# hacking_the_simplespectro.net
KiCad netlist of a schematic drawn in EAGLE
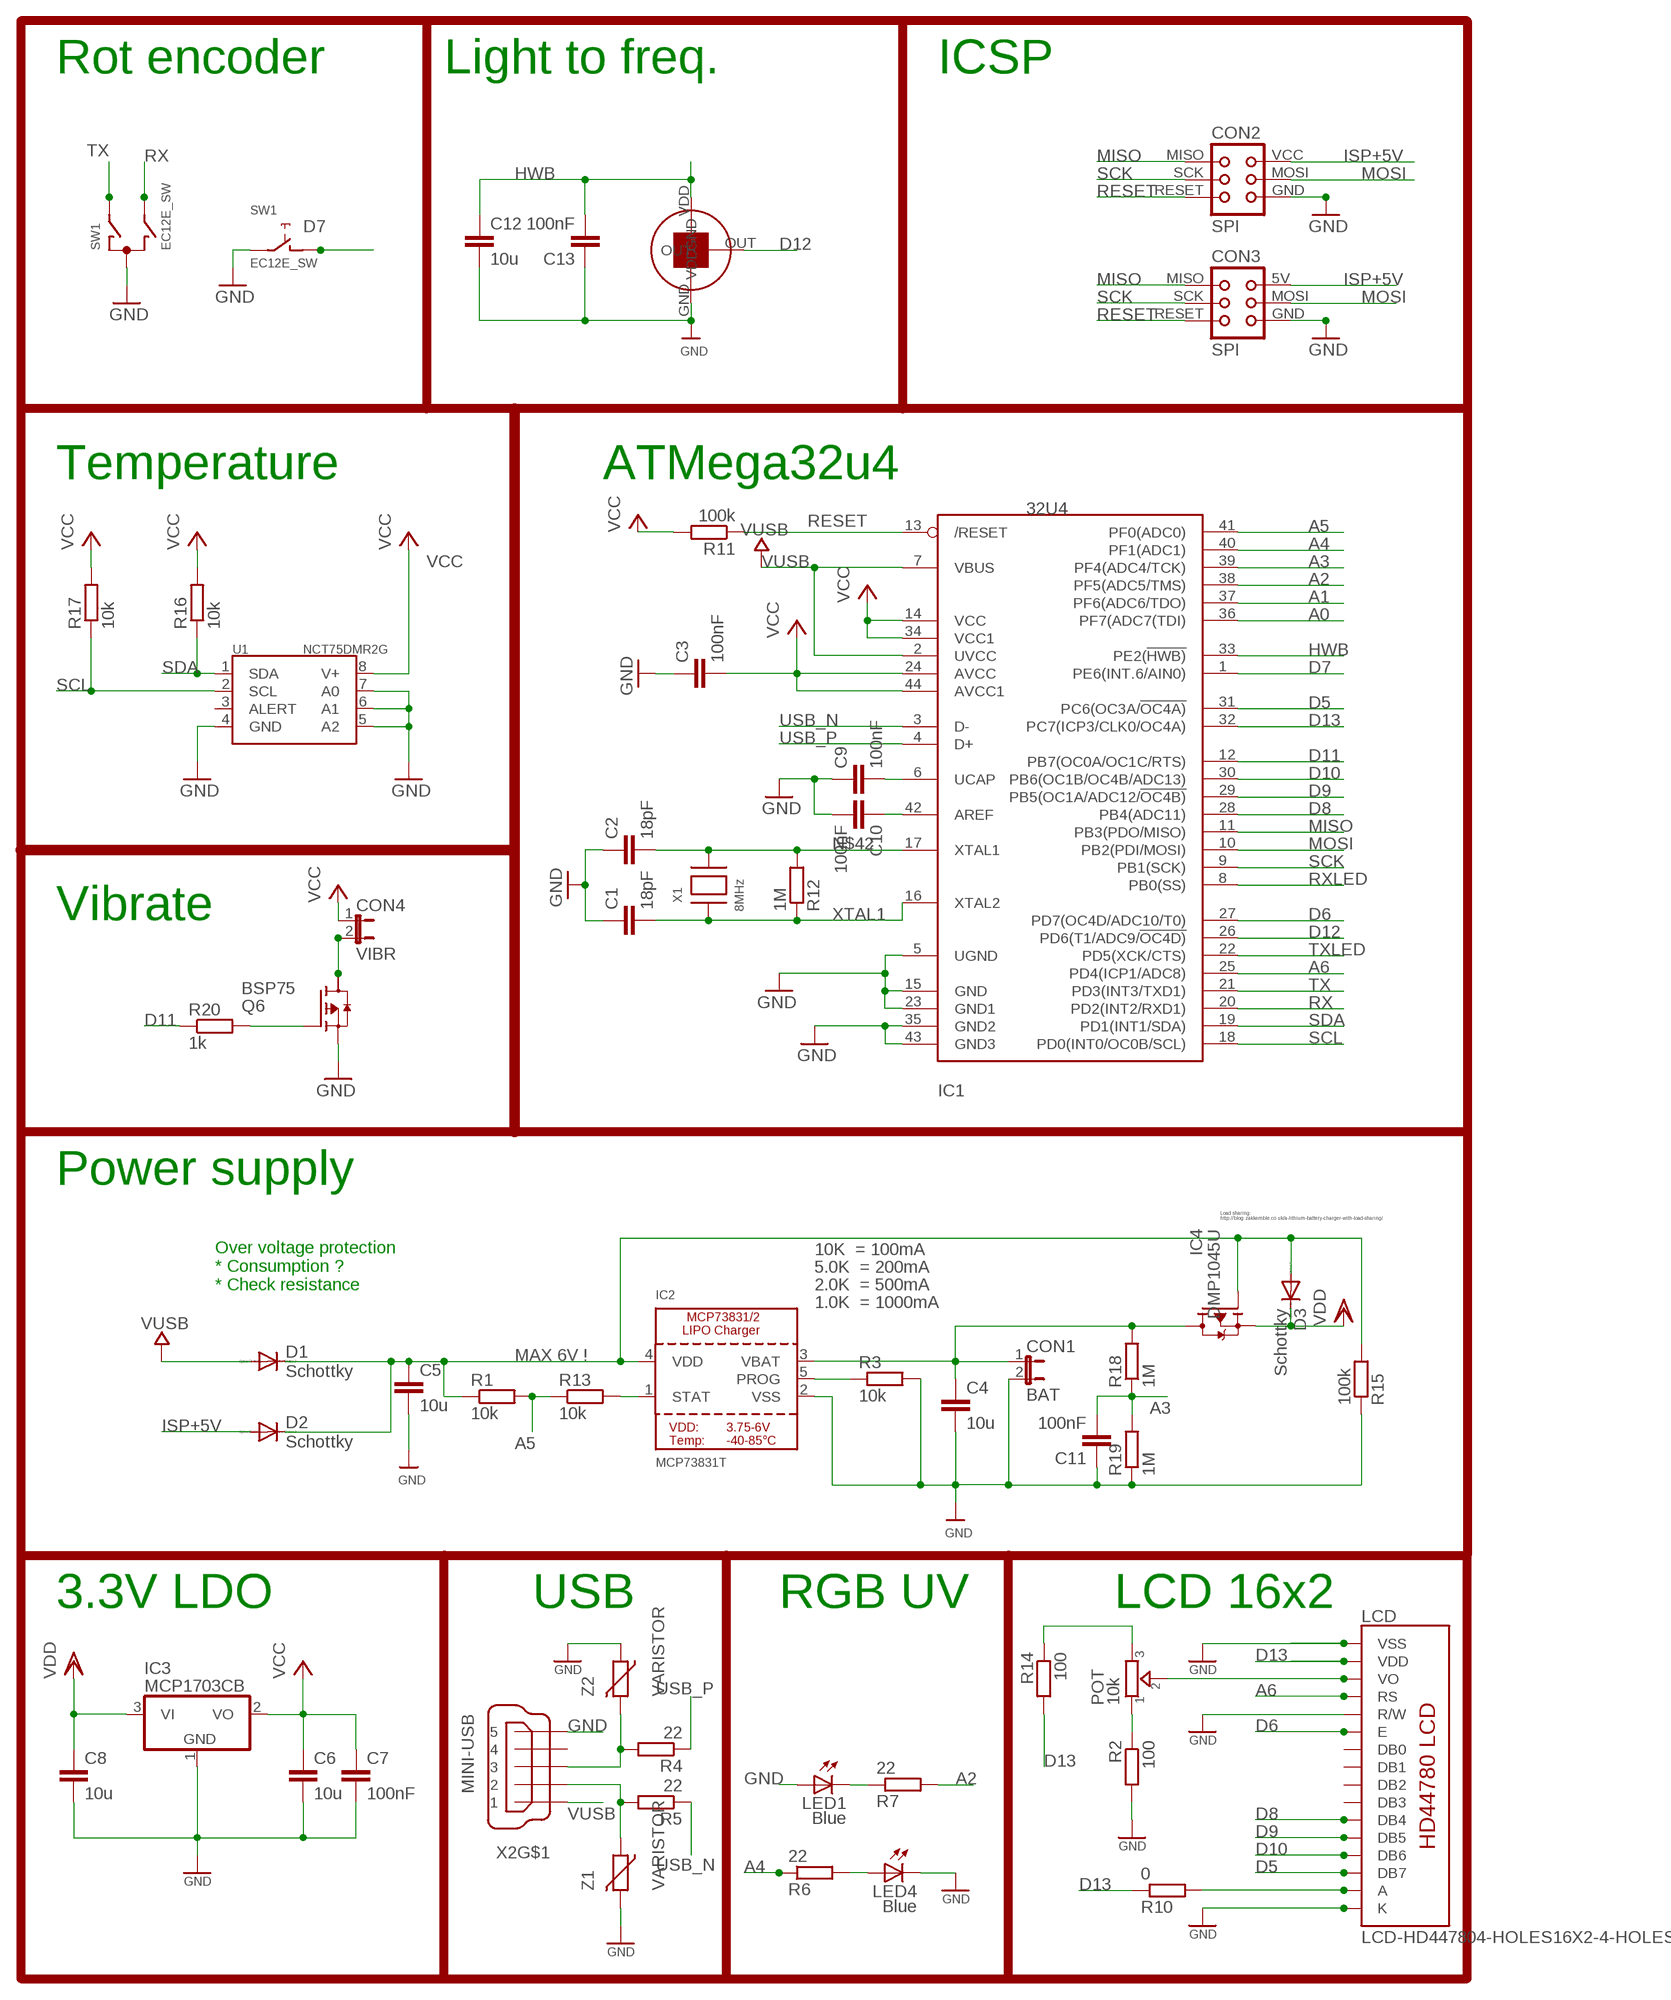
[diagram p0: schematic, sheet 1]

(export (version "E")
  (design (tool "Eeschema 10.0.6"))
  (components
    (comp (ref "C1")
      (value "18pF")
      (footprint "eagle-import:C0805K")
      (fields (field (name "MPN") "77-VJ1206A180JXXPBC"))
      (libsource (lib "eagle-import") (part "C-EUC0805K"))
    )
    (comp (ref "C2")
      (value "18pF")
      (footprint "eagle-import:C0805K")
      (fields (field (name "MPN") "77-VJ1206A180JXXPBC"))
      (libsource (lib "eagle-import") (part "C-EUC0805K"))
    )
    (comp (ref "C3")
      (value "100nF")
      (footprint "eagle-import:C0805K")
      (fields (field (name "MPN") "80-C1206C104K5R"))
      (libsource (lib "eagle-import") (part "C-EUC0805K"))
    )
    (comp (ref "C4")
      (value "10u")
      (footprint "eagle-import:C0805K")
      (fields (field (name "MPN") "77-VJ1206V106ZXQTBC"))
      (libsource (lib "eagle-import") (part "C-EUC0805K"))
    )
    (comp (ref "C5")
      (value "10u")
      (footprint "eagle-import:C0805K")
      (fields (field (name "MPN") "77-VJ1206V106ZXQTBC"))
      (libsource (lib "eagle-import") (part "C-EUC0805K"))
    )
    (comp (ref "C6")
      (value "10u")
      (footprint "eagle-import:C0805K")
      (fields (field (name "MPN") "77-VJ1206V106ZXQTBC"))
      (libsource (lib "eagle-import") (part "C-EUC0805K"))
    )
    (comp (ref "C7")
      (value "100nF")
      (footprint "eagle-import:C0805K")
      (fields (field (name "MPN") "80-C1206C104K5R"))
      (libsource (lib "eagle-import") (part "C-EUC0805K"))
    )
    (comp (ref "C8")
      (value "10u")
      (footprint "eagle-import:C0805K")
      (fields (field (name "MPN") "77-VJ1206V106ZXQTBC"))
      (libsource (lib "eagle-import") (part "C-EUC0805K"))
    )
    (comp (ref "C9")
      (value "100nF")
      (footprint "eagle-import:C0805K")
      (fields (field (name "MPN") "80-C1206C104K5R"))
      (libsource (lib "eagle-import") (part "C-EUC0805K"))
    )
    (comp (ref "C10")
      (value "100nF")
      (footprint "eagle-import:C0805K")
      (fields (field (name "MPN") "80-C1206C104K5R"))
      (libsource (lib "eagle-import") (part "C-EUC0805K"))
    )
    (comp (ref "C11")
      (value "100nF")
      (footprint "eagle-import:C0805K")
      (fields (field (name "MPN") "80-C1206C104K5R"))
      (libsource (lib "eagle-import") (part "C-EUC0805K"))
    )
    (comp (ref "C12")
      (value "10u")
      (footprint "eagle-import:C0805K")
      (fields (field (name "MPN") "77-VJ1206V106ZXQTBC"))
      (libsource (lib "eagle-import") (part "C-EUC0805K"))
    )
    (comp (ref "C13")
      (value "100nF")
      (footprint "eagle-import:C0805K")
      (fields (field (name "MPN") "80-C1206C104K5R"))
      (libsource (lib "eagle-import") (part "C-EUC0805K"))
    )
    (comp (ref "CON1")
      (value "BAT")
      (footprint "eagle-import:JP1")
      (libsource (lib "eagle-import") (part "JP1E"))
    )
    (comp (ref "CON2")
      (value "SPI")
      (footprint "eagle-import:TINYISP")
      (libsource (lib "eagle-import") (part "TINYISP"))
    )
    (comp (ref "CON3")
      (value "SPI")
      (footprint "eagle-import:TC2030-MCP-NL")
      (libsource (lib "eagle-import") (part "TINYISPT"))
    )
    (comp (ref "CON4")
      (value "VIBR")
      (footprint "eagle-import:JP1")
      (libsource (lib "eagle-import") (part "JP1E"))
    )
    (comp (ref "D1")
      (value "Schottky")
      (footprint "eagle-import:SOD123")
      (fields (field (name "MPN") "621-1N5819HW-F"))
      (libsource (lib "eagle-import") (part "MBR0520LT"))
    )
    (comp (ref "D2")
      (value "Schottky")
      (footprint "eagle-import:SOD123")
      (fields (field (name "MPN") "621-1N5819HW-F"))
      (libsource (lib "eagle-import") (part "MBR0520LT"))
    )
    (comp (ref "D3")
      (value "Schottky")
      (footprint "eagle-import:SOD123")
      (fields (field (name "MPN") "621-1N5819HW-F"))
      (libsource (lib "eagle-import") (part "MBR0520LT"))
    )
    (comp (ref "IC1")
      (value "32U4")
      (footprint "eagle-import:TQFP44")
      (fields (field (name "MPN") "556-ATMEGA32U4RC-AU"))
      (libsource (lib "eagle-import") (part "ATMEGA32U4-AU"))
    )
    (comp (ref "IC2")
      (value "MCP73831T")
      (footprint "eagle-import:SOT23-5")
      (fields (field (name "MPN") "579-MCP73831T-3ACIOT"))
      (libsource (lib "eagle-import") (part "MCP73831/2"))
    )
    (comp (ref "IC3")
      (value "MCP1703CB")
      (footprint "eagle-import:SOT23")
      (libsource (lib "eagle-import") (part "MCP1703CB"))
    )
    (comp (ref "IC4")
      (value "DMP1045U")
      (footprint "eagle-import:SOT-23")
      (fields (field (name "MPN") "621-DMP1045U-7"))
      (libsource (lib "eagle-import") (part "TRANSISTOR_FET_TSM2301CX"))
    )
    (comp (ref "LCD")
      (value "LCD-HD447804-HOLES16X2-4-HOLES")
      (footprint "eagle-import:LCD-16X2-4HOLES")
      (libsource (lib "eagle-import") (part "LCD-HD4478016X2-4-HOLES4-HOLES"))
    )
    (comp (ref "LED1")
      (value "Blue")
      (footprint "eagle-import:LED5MM")
      (libsource (lib "eagle-import") (part "LED5MM"))
    )
    (comp (ref "LED4")
      (value "Blue")
      (footprint "eagle-import:LED5MM")
      (libsource (lib "eagle-import") (part "LED5MM"))
    )
    (comp (ref "POT")
      (value "10k")
      (footprint "eagle-import:TRIMMER_3362P")
      (libsource (lib "eagle-import") (part "TRIMMER-3362P"))
    )
    (comp (ref "Q6")
      (value "BSP75")
      (footprint "eagle-import:PG-SOT-223")
      (libsource (lib "eagle-import") (part "BSP75"))
    )
    (comp (ref "R1")
      (value "10k")
      (footprint "eagle-import:R0805")
      (libsource (lib "eagle-import") (part "R-EU_R0805"))
    )
    (comp (ref "R2")
      (value "100")
      (footprint "eagle-import:R0805")
      (libsource (lib "eagle-import") (part "R-EU_R0805"))
    )
    (comp (ref "R3")
      (value "10k")
      (footprint "eagle-import:R0805")
      (libsource (lib "eagle-import") (part "R-EU_R0805"))
    )
    (comp (ref "R4")
      (value "22")
      (footprint "eagle-import:R0805")
      (libsource (lib "eagle-import") (part "R-EU_R0805"))
    )
    (comp (ref "R5")
      (value "22")
      (footprint "eagle-import:R0805")
      (libsource (lib "eagle-import") (part "rcl_334_R-EU_R0805"))
    )
    (comp (ref "R6")
      (value "22")
      (footprint "eagle-import:R0805")
      (fields (field (name "MPN") "667-ERJ-8GEYJ101V"))
      (libsource (lib "eagle-import") (part "R-EU_R0805"))
    )
    (comp (ref "R7")
      (value "22")
      (footprint "eagle-import:R0805")
      (libsource (lib "eagle-import") (part "R-EU_R0805"))
    )
    (comp (ref "R10")
      (value "0")
      (footprint "eagle-import:R0805")
      (libsource (lib "eagle-import") (part "rcl_334_R-EU_R0805"))
    )
    (comp (ref "R11")
      (value "100k")
      (footprint "eagle-import:R0805")
      (fields (field (name "MPN") "RC1206FR-07100KL"))
      (libsource (lib "eagle-import") (part "rcl_334_R-EU_R0805"))
    )
    (comp (ref "R12")
      (value "1M")
      (footprint "eagle-import:R0805")
      (libsource (lib "eagle-import") (part "R-EU_R0805"))
    )
    (comp (ref "R13")
      (value "10k")
      (footprint "eagle-import:R0805")
      (libsource (lib "eagle-import") (part "R-EU_R0805"))
    )
    (comp (ref "R14")
      (value "100")
      (footprint "eagle-import:R0805")
      (libsource (lib "eagle-import") (part "R-EU_R0805"))
    )
    (comp (ref "R15")
      (value "100k")
      (footprint "eagle-import:R0805")
      (fields (field (name "MPN") "RC1206FR-07100KL"))
      (libsource (lib "eagle-import") (part "R-EU_R0805"))
    )
    (comp (ref "R16")
      (value "10k")
      (footprint "eagle-import:R0805")
      (libsource (lib "eagle-import") (part "R-EU_R0805"))
    )
    (comp (ref "R17")
      (value "10k")
      (footprint "eagle-import:R0805")
      (libsource (lib "eagle-import") (part "R-EU_R0805"))
    )
    (comp (ref "R18")
      (value "1M")
      (footprint "eagle-import:R0805")
      (libsource (lib "eagle-import") (part "R-EU_R0805"))
    )
    (comp (ref "R19")
      (value "1M")
      (footprint "eagle-import:R0805")
      (libsource (lib "eagle-import") (part "R-EU_R0805"))
    )
    (comp (ref "R20")
      (value "1k")
      (footprint "eagle-import:R0805")
      (libsource (lib "eagle-import") (part "R-EU_R0805"))
    )
    (comp (ref "SW1")
      (value "EC12E_SW")
      (footprint "eagle-import:ALPS_EC12E_SW")
      (fields (field (name "MPN") "EC12E2424407"))
      (libsource (lib "eagle-import") (part "EC12E_SW"))
    )
    (comp (ref "U$7")
      (value "TSL237")
      (footprint "eagle-import:TSL237")
      (libsource (lib "eagle-import") (part "TSL237"))
    )
    (comp (ref "U1")
      (value "NCT75DMR2G")
      (footprint "eagle-import:MSOP8")
      (libsource (lib "eagle-import") (part "TMP75DGK"))
    )
    (comp (ref "X1")
      (value "8MHz")
      (footprint "eagle-import:NX6035")
      (fields (field (name "MPN") "729-F60800010"))
      (libsource (lib "eagle-import") (part "XTALNX6035"))
    )
    (comp (ref "X2")
      (value "MINI-USB")
      (footprint "eagle-import:32005-201")
      (fields (field (name "MPN") "649-10033526-N3212LF"))
      (libsource (lib "eagle-import") (part "MINI-USB-SCHIELD-32005-201"))
    )
    (comp (ref "Z1")
      (value "VARISTOR")
      (footprint "eagle-import:CT_CN0603")
      (libsource (lib "eagle-import") (part "VARISTORCN0603"))
    )
    (comp (ref "Z2")
      (value "VARISTOR")
      (footprint "eagle-import:CT_CN0603")
      (libsource (lib "eagle-import") (part "VARISTORCN0603"))
    )
  )
  (nets
    (net (code "1") (name "/A0") (class "Default")
      (node (ref "IC1") (pin "36") (pinfunction "PF7(ADC7(TDI)_36") (pintype "bidirectional"))
    )
    (net (code "2") (name "/A1") (class "Default")
      (node (ref "IC1") (pin "37") (pinfunction "PF6(ADC6/TDO)_37") (pintype "bidirectional"))
    )
    (net (code "3") (name "/A2") (class "Default")
      (node (ref "IC1") (pin "38") (pinfunction "PF5(ADC5/TMS)_38") (pintype "bidirectional"))
      (node (ref "R7") (pin "2") (pinfunction "2_2") (pintype "passive"))
    )
    (net (code "4") (name "/A3") (class "Default")
      (node (ref "C11") (pin "2") (pinfunction "2_2") (pintype "passive"))
      (node (ref "IC1") (pin "39") (pinfunction "PF4(ADC4/TCK)_39") (pintype "bidirectional"))
      (node (ref "R18") (pin "1") (pinfunction "1_1") (pintype "passive"))
      (node (ref "R19") (pin "2") (pinfunction "2_2") (pintype "passive"))
    )
    (net (code "5") (name "/A4") (class "Default")
      (node (ref "IC1") (pin "40") (pinfunction "PF1(ADC1)_40") (pintype "bidirectional"))
      (node (ref "R6") (pin "1") (pinfunction "1_1") (pintype "passive"))
    )
    (net (code "6") (name "/A5") (class "Default")
      (node (ref "IC1") (pin "41") (pinfunction "PF0(ADC0)_41") (pintype "bidirectional"))
      (node (ref "R1") (pin "2") (pinfunction "2_2") (pintype "passive"))
      (node (ref "R13") (pin "1") (pinfunction "1_1") (pintype "passive"))
    )
    (net (code "7") (name "/A6") (class "Default")
      (node (ref "IC1") (pin "25") (pinfunction "PD4(ICP1/ADC8)_25") (pintype "bidirectional"))
      (node (ref "LCD") (pin "4") (pinfunction "RS_4") (pintype "input"))
    )
    (net (code "8") (name "/D5") (class "Default")
      (node (ref "IC1") (pin "31") (pinfunction "PC6(OC3A/~{OC4A})_31") (pintype "bidirectional"))
      (node (ref "LCD") (pin "14") (pinfunction "DB7_14") (pintype "bidirectional"))
    )
    (net (code "9") (name "/D6") (class "Default")
      (node (ref "IC1") (pin "27") (pinfunction "PD7(OC4D/ADC10/T0)_27") (pintype "bidirectional"))
      (node (ref "LCD") (pin "6") (pinfunction "E_6") (pintype "input"))
    )
    (net (code "10") (name "/D7") (class "Default")
      (node (ref "IC1") (pin "1") (pinfunction "PE6(INT.6/AIN0)_1") (pintype "bidirectional"))
      (node (ref "SW1") (pin "D") (pinfunction "1_D") (pintype "passive"))
    )
    (net (code "11") (name "/D8") (class "Default")
      (node (ref "IC1") (pin "28") (pinfunction "PB4(ADC11)_28") (pintype "bidirectional"))
      (node (ref "LCD") (pin "11") (pinfunction "DB4_11") (pintype "bidirectional"))
    )
    (net (code "12") (name "/D9") (class "Default")
      (node (ref "IC1") (pin "29") (pinfunction "PB5(OC1A/ADC12/~{OC4B})_29") (pintype "bidirectional"))
      (node (ref "LCD") (pin "12") (pinfunction "DB5_12") (pintype "bidirectional"))
    )
    (net (code "13") (name "/D10") (class "Default")
      (node (ref "IC1") (pin "30") (pinfunction "PB6(OC1B/OC4B/ADC13)_30") (pintype "bidirectional"))
      (node (ref "LCD") (pin "13") (pinfunction "DB6_13") (pintype "bidirectional"))
    )
    (net (code "14") (name "/D11") (class "Default")
      (node (ref "IC1") (pin "12") (pinfunction "PB7(OC0A/OC1C/RTS)_12") (pintype "bidirectional"))
      (node (ref "R20") (pin "1") (pinfunction "1_1") (pintype "passive"))
    )
    (net (code "15") (name "/D12") (class "Default")
      (node (ref "IC1") (pin "26") (pinfunction "PD6(T1/ADC9/~{OC4D})_26") (pintype "bidirectional"))
      (node (ref "U$7") (pin "OUT") (pinfunction "OUT_OUT") (pintype "output"))
    )
    (net (code "16") (name "/D13") (class "Default")
      (node (ref "IC1") (pin "32") (pinfunction "PC7(ICP3/CLK0/OC4A)_32") (pintype "bidirectional"))
      (node (ref "LCD") (pin "2") (pinfunction "VDD_2") (pintype "power_in"))
      (node (ref "R10") (pin "1") (pinfunction "1_1") (pintype "passive"))
      (node (ref "R14") (pin "2") (pinfunction "2_2") (pintype "passive"))
    )
    (net (code "17") (name "/HWB") (class "Default")
      (node (ref "C12") (pin "1") (pinfunction "1_1") (pintype "passive"))
      (node (ref "C13") (pin "2") (pinfunction "2_2") (pintype "passive"))
      (node (ref "IC1") (pin "33") (pinfunction "PE2(~{HWB})_33") (pintype "bidirectional"))
      (node (ref "U$7") (pin "VDD") (pinfunction "VDD_VDD") (pintype "power_in"))
    )
    (net (code "18") (name "/ISP+5V") (class "Default")
      (node (ref "CON2") (pin "VCC") (pinfunction "VCC_VCC") (pintype "passive"))
      (node (ref "CON3") (pin "5V") (pinfunction "VCC_5V") (pintype "passive"))
      (node (ref "D2") (pin "A") (pinfunction "A_A") (pintype "passive"))
    )
    (net (code "19") (name "/MISO") (class "Default")
      (node (ref "CON2") (pin "MISO") (pinfunction "MISO_MISO") (pintype "passive"))
      (node (ref "CON3") (pin "MISO") (pinfunction "MISO_MISO") (pintype "passive"))
      (node (ref "IC1") (pin "11") (pinfunction "PB3(PDO/MISO)_11") (pintype "bidirectional"))
    )
    (net (code "20") (name "/MOSI") (class "Default")
      (node (ref "CON2") (pin "MOSI") (pinfunction "MOSI_MOSI") (pintype "passive"))
      (node (ref "CON3") (pin "MOSI") (pinfunction "MOSI_MOSI") (pintype "passive"))
      (node (ref "IC1") (pin "10") (pinfunction "PB2(PDI/MOSI)_10") (pintype "bidirectional"))
    )
    (net (code "21") (name "/N$42") (class "Default")
      (node (ref "C2") (pin "2") (pinfunction "2_2") (pintype "passive"))
      (node (ref "IC1") (pin "17") (pinfunction "XTAL1_17") (pintype "bidirectional"))
      (node (ref "R12") (pin "2") (pinfunction "2_2") (pintype "passive"))
      (node (ref "X1") (pin "P$2") (pinfunction "P$2_P$2") (pintype "bidirectional"))
    )
    (net (code "22") (name "/RESET") (class "Default")
      (node (ref "CON2") (pin "RESET") (pinfunction "RESET_RESET") (pintype "passive"))
      (node (ref "CON3") (pin "RESET") (pinfunction "RESET_RESET") (pintype "passive"))
      (node (ref "IC1") (pin "13") (pinfunction "/RESET_13") (pintype "bidirectional"))
      (node (ref "R11") (pin "1") (pinfunction "1_1") (pintype "passive"))
    )
    (net (code "23") (name "/RX") (class "Default")
      (node (ref "IC1") (pin "20") (pinfunction "PD2(INT2/RXD1)_20") (pintype "bidirectional"))
      (node (ref "SW1") (pin "B") (pinfunction "B_B") (pintype "passive"))
    )
    (net (code "24") (name "/RXLED") (class "Default")
      (node (ref "IC1") (pin "8") (pinfunction "PB0(SS)_8") (pintype "bidirectional"))
    )
    (net (code "25") (name "/SCK") (class "Default")
      (node (ref "CON2") (pin "SCK") (pinfunction "SCK_SCK") (pintype "passive"))
      (node (ref "CON3") (pin "SCK") (pinfunction "SCK_SCK") (pintype "passive"))
      (node (ref "IC1") (pin "9") (pinfunction "PB1(SCK)_9") (pintype "bidirectional"))
    )
    (net (code "26") (name "/SCL") (class "Default")
      (node (ref "IC1") (pin "18") (pinfunction "PD0(INT0/OC0B/SCL)_18") (pintype "bidirectional"))
      (node (ref "R17") (pin "1") (pinfunction "1_1") (pintype "passive"))
      (node (ref "U1") (pin "2") (pinfunction "SCL_2") (pintype "bidirectional"))
    )
    (net (code "27") (name "/SDA") (class "Default")
      (node (ref "IC1") (pin "19") (pinfunction "PD1(INT1/SDA)_19") (pintype "bidirectional"))
      (node (ref "R16") (pin "1") (pinfunction "1_1") (pintype "passive"))
      (node (ref "U1") (pin "1") (pinfunction "SDA_1") (pintype "bidirectional"))
    )
    (net (code "28") (name "/TX") (class "Default")
      (node (ref "IC1") (pin "21") (pinfunction "PD3(INT3/TXD1)_21") (pintype "bidirectional"))
      (node (ref "SW1") (pin "A") (pinfunction "A_A") (pintype "passive"))
    )
    (net (code "29") (name "/TXLED") (class "Default")
      (node (ref "IC1") (pin "22") (pinfunction "PD5(XCK/CTS)_22") (pintype "bidirectional"))
    )
    (net (code "30") (name "/USB_N") (class "Default")
      (node (ref "IC1") (pin "3") (pinfunction "D-_3") (pintype "bidirectional"))
      (node (ref "R5") (pin "1") (pinfunction "1_1") (pintype "passive"))
    )
    (net (code "31") (name "/USB_P") (class "Default")
      (node (ref "IC1") (pin "4") (pinfunction "D+_4") (pintype "bidirectional"))
      (node (ref "R4") (pin "1") (pinfunction "1_1") (pintype "passive"))
    )
    (net (code "32") (name "/XTAL1") (class "Default")
      (node (ref "C1") (pin "2") (pinfunction "2_2") (pintype "passive"))
      (node (ref "IC1") (pin "16") (pinfunction "XTAL2_16") (pintype "bidirectional"))
      (node (ref "R12") (pin "1") (pinfunction "1_1") (pintype "passive"))
      (node (ref "X1") (pin "P$1") (pinfunction "P$1_P$1") (pintype "bidirectional"))
    )
    (net (code "33") (name "GND") (class "Default")
      (node (ref "C1") (pin "1") (pinfunction "1_1") (pintype "passive"))
      (node (ref "C10") (pin "2") (pinfunction "2_2") (pintype "passive"))
      (node (ref "C11") (pin "1") (pinfunction "1_1") (pintype "passive"))
      (node (ref "C12") (pin "2") (pinfunction "2_2") (pintype "passive"))
      (node (ref "C13") (pin "1") (pinfunction "1_1") (pintype "passive"))
      (node (ref "C2") (pin "1") (pinfunction "1_1") (pintype "passive"))
      (node (ref "C3") (pin "1") (pinfunction "1_1") (pintype "passive"))
      (node (ref "C4") (pin "2") (pinfunction "2_2") (pintype "passive"))
      (node (ref "C5") (pin "2") (pinfunction "2_2") (pintype "passive"))
      (node (ref "C6") (pin "2") (pinfunction "2_2") (pintype "passive"))
      (node (ref "C7") (pin "2") (pinfunction "2_2") (pintype "passive"))
      (node (ref "C8") (pin "2") (pinfunction "2_2") (pintype "passive"))
      (node (ref "C9") (pin "1") (pinfunction "1_1") (pintype "passive"))
      (node (ref "CON1") (pin "2") (pinfunction "2_2") (pintype "passive"))
      (node (ref "CON2") (pin "GND") (pinfunction "GND_GND") (pintype "passive"))
      (node (ref "CON3") (pin "GND") (pinfunction "GND_GND") (pintype "passive"))
      (node (ref "IC1") (pin "15") (pinfunction "GND_15") (pintype "bidirectional"))
      (node (ref "IC1") (pin "23") (pinfunction "GND1_23") (pintype "bidirectional"))
      (node (ref "IC1") (pin "35") (pinfunction "GND2_35") (pintype "bidirectional"))
      (node (ref "IC1") (pin "43") (pinfunction "GND3_43") (pintype "bidirectional"))
      (node (ref "IC1") (pin "5") (pinfunction "UGND_5") (pintype "bidirectional"))
      (node (ref "IC2") (pin "2") (pinfunction "VSS_2") (pintype "power_in"))
      (node (ref "IC3") (pin "1") (pinfunction "GND_1") (pintype "passive"))
      (node (ref "LCD") (pin "1") (pinfunction "VSS_1") (pintype "power_in"))
      (node (ref "LCD") (pin "16") (pinfunction "K_16") (pintype "power_in"))
      (node (ref "LCD") (pin "5") (pinfunction "R/W_5") (pintype "input"))
      (node (ref "LED1") (pin "A") (pinfunction "A_A") (pintype "passive"))
      (node (ref "LED4") (pin "K") (pinfunction "C_K") (pintype "passive"))
      (node (ref "Q6") (pin "3") (pinfunction "S_3") (pintype "passive"))
      (node (ref "R15") (pin "1") (pinfunction "1_1") (pintype "passive"))
      (node (ref "R19") (pin "1") (pinfunction "1_1") (pintype "passive"))
      (node (ref "R2") (pin "2") (pinfunction "2_2") (pintype "passive"))
      (node (ref "R3") (pin "2") (pinfunction "2_2") (pintype "passive"))
      (node (ref "SW1") (pin "C") (pinfunction "C_C") (pintype "passive"))
      (node (ref "SW1") (pin "E") (pinfunction "2_E") (pintype "passive"))
      (node (ref "U$7") (pin "GND") (pinfunction "GND_GND") (pintype "power_in"))
      (node (ref "U1") (pin "4") (pinfunction "GND_4") (pintype "bidirectional"))
      (node (ref "U1") (pin "5") (pinfunction "A2_5") (pintype "bidirectional"))
      (node (ref "U1") (pin "6") (pinfunction "A1_6") (pintype "bidirectional"))
      (node (ref "U1") (pin "7") (pinfunction "A0_7") (pintype "bidirectional"))
      (node (ref "X2") (pin "5") (pinfunction "5_5") (pintype "passive"))
      (node (ref "Z1") (pin "2") (pinfunction "2_2") (pintype "passive"))
      (node (ref "Z2") (pin "1") (pinfunction "1_1") (pintype "passive"))
    )
    (net (code "34") (name "Net-(CON4-Pad2)") (class "Default")
      (node (ref "CON4") (pin "2") (pinfunction "2_2") (pintype "passive"))
      (node (ref "Q6") (pin "2") (pinfunction "D_2") (pintype "passive"))
    )
    (net (code "35") (name "Net-(IC1-AREF)") (class "Default")
      (node (ref "C10") (pin "1") (pinfunction "1_1") (pintype "passive"))
      (node (ref "IC1") (pin "42") (pinfunction "AREF_42") (pintype "bidirectional"))
    )
    (net (code "36") (name "Net-(IC1-UCAP)") (class "Default")
      (node (ref "C9") (pin "2") (pinfunction "2_2") (pintype "passive"))
      (node (ref "IC1") (pin "6") (pinfunction "UCAP_6") (pintype "bidirectional"))
    )
    (net (code "37") (name "Net-(IC2-PROG)") (class "Default")
      (node (ref "IC2") (pin "5") (pinfunction "PROG_5") (pintype "input"))
      (node (ref "R3") (pin "1") (pinfunction "1_1") (pintype "passive"))
    )
    (net (code "38") (name "Net-(IC2-STAT)") (class "Default")
      (node (ref "IC2") (pin "1") (pinfunction "STAT_1") (pintype "output"))
      (node (ref "R13") (pin "2") (pinfunction "2_2") (pintype "passive"))
    )
    (net (code "39") (name "Net-(IC2-VBAT)") (class "Default")
      (node (ref "C4") (pin "1") (pinfunction "1_1") (pintype "passive"))
      (node (ref "CON1") (pin "1") (pinfunction "1_1") (pintype "passive"))
      (node (ref "IC2") (pin "3") (pinfunction "VBAT_3") (pintype "power_in"))
      (node (ref "IC4") (pin "3") (pinfunction "D_3") (pintype "passive"))
      (node (ref "R18") (pin "2") (pinfunction "2_2") (pintype "passive"))
    )
    (net (code "40") (name "Net-(IC2-VDD)") (class "Default")
      (node (ref "C5") (pin "1") (pinfunction "1_1") (pintype "passive"))
      (node (ref "D1") (pin "C") (pinfunction "C_C") (pintype "passive"))
      (node (ref "D2") (pin "C") (pinfunction "C_C") (pintype "passive"))
      (node (ref "D3") (pin "A") (pinfunction "A_A") (pintype "passive"))
      (node (ref "IC2") (pin "4") (pinfunction "VDD_4") (pintype "power_in"))
      (node (ref "IC4") (pin "1") (pinfunction "G_1") (pintype "passive"))
      (node (ref "R1") (pin "1") (pinfunction "1_1") (pintype "passive"))
      (node (ref "R15") (pin "2") (pinfunction "2_2") (pintype "passive"))
    )
    (net (code "41") (name "Net-(LCD-A)") (class "Default")
      (node (ref "LCD") (pin "15") (pinfunction "A_15") (pintype "power_in"))
      (node (ref "R10") (pin "2") (pinfunction "2_2") (pintype "passive"))
    )
    (net (code "42") (name "Net-(LCD-VO)") (class "Default")
      (node (ref "LCD") (pin "3") (pinfunction "VO_3") (pintype "bidirectional"))
      (node (ref "POT") (pin "2") (pinfunction "2_2") (pintype "passive"))
    )
    (net (code "43") (name "Net-(LED1-C)") (class "Default")
      (node (ref "LED1") (pin "K") (pinfunction "C_K") (pintype "passive"))
      (node (ref "R7") (pin "1") (pinfunction "1_1") (pintype "passive"))
    )
    (net (code "44") (name "Net-(LED4-PadA)") (class "Default")
      (node (ref "LED4") (pin "A") (pinfunction "A_A") (pintype "passive"))
      (node (ref "R6") (pin "2") (pinfunction "2_2") (pintype "passive"))
    )
    (net (code "45") (name "Net-(POT-Pad1)") (class "Default")
      (node (ref "POT") (pin "1") (pinfunction "1_1") (pintype "passive"))
      (node (ref "R2") (pin "1") (pinfunction "1_1") (pintype "passive"))
    )
    (net (code "46") (name "Net-(POT-Pad3)") (class "Default")
      (node (ref "POT") (pin "3") (pinfunction "3_3") (pintype "passive"))
      (node (ref "R14") (pin "1") (pinfunction "1_1") (pintype "passive"))
    )
    (net (code "47") (name "Net-(Q6-G)") (class "Default")
      (node (ref "Q6") (pin "1") (pinfunction "G_1") (pintype "passive"))
      (node (ref "R20") (pin "2") (pinfunction "2_2") (pintype "passive"))
    )
    (net (code "48") (name "Net-(R4-Pad2)") (class "Default")
      (node (ref "R4") (pin "2") (pinfunction "2_2") (pintype "passive"))
      (node (ref "X2") (pin "3") (pinfunction "3_3") (pintype "passive"))
      (node (ref "Z2") (pin "2") (pinfunction "2_2") (pintype "passive"))
    )
    (net (code "49") (name "Net-(R5-Pad2)") (class "Default")
      (node (ref "R5") (pin "2") (pinfunction "2_2") (pintype "passive"))
      (node (ref "X2") (pin "2") (pinfunction "2_2") (pintype "passive"))
      (node (ref "Z1") (pin "1") (pinfunction "1_1") (pintype "passive"))
    )
    (net (code "50") (name "VCC") (class "Default")
      (node (ref "C3") (pin "2") (pinfunction "2_2") (pintype "passive"))
      (node (ref "C6") (pin "1") (pinfunction "1_1") (pintype "passive"))
      (node (ref "C7") (pin "1") (pinfunction "1_1") (pintype "passive"))
      (node (ref "CON4") (pin "1") (pinfunction "1_1") (pintype "passive"))
      (node (ref "IC1") (pin "14") (pinfunction "VCC_14") (pintype "bidirectional"))
      (node (ref "IC1") (pin "24") (pinfunction "AVCC_24") (pintype "bidirectional"))
      (node (ref "IC1") (pin "34") (pinfunction "VCC1_34") (pintype "bidirectional"))
      (node (ref "IC1") (pin "44") (pinfunction "AVCC1_44") (pintype "bidirectional"))
      (node (ref "IC3") (pin "2") (pinfunction "VO_2") (pintype "passive"))
      (node (ref "R11") (pin "2") (pinfunction "2_2") (pintype "passive"))
      (node (ref "R16") (pin "2") (pinfunction "2_2") (pintype "passive"))
      (node (ref "R17") (pin "2") (pinfunction "2_2") (pintype "passive"))
      (node (ref "U1") (pin "8") (pinfunction "V+_8") (pintype "bidirectional"))
    )
    (net (code "51") (name "VDD") (class "Default")
      (node (ref "C8") (pin "1") (pinfunction "1_1") (pintype "passive"))
      (node (ref "D3") (pin "C") (pinfunction "C_C") (pintype "passive"))
      (node (ref "IC3") (pin "3") (pinfunction "VI_3") (pintype "input"))
      (node (ref "IC4") (pin "2") (pinfunction "S_2") (pintype "passive"))
    )
    (net (code "52") (name "VUSB") (class "Default")
      (node (ref "D1") (pin "A") (pinfunction "A_A") (pintype "passive"))
      (node (ref "IC1") (pin "2") (pinfunction "UVCC_2") (pintype "bidirectional"))
      (node (ref "IC1") (pin "7") (pinfunction "VBUS_7") (pintype "bidirectional"))
      (node (ref "X2") (pin "1") (pinfunction "1_1") (pintype "passive"))
    )
    (net (code "53") (name "unconnected-(LCD-DB0-Pad7)") (class "Default")
      (node (ref "LCD") (pin "7") (pinfunction "DB0_7") (pintype "bidirectional"))
    )
    (net (code "54") (name "unconnected-(LCD-DB1-Pad8)") (class "Default")
      (node (ref "LCD") (pin "8") (pinfunction "DB1_8") (pintype "bidirectional"))
    )
    (net (code "55") (name "unconnected-(LCD-DB2-Pad9)") (class "Default")
      (node (ref "LCD") (pin "9") (pinfunction "DB2_9") (pintype "bidirectional"))
    )
    (net (code "56") (name "unconnected-(LCD-DB3-Pad10)") (class "Default")
      (node (ref "LCD") (pin "10") (pinfunction "DB3_10") (pintype "bidirectional"))
    )
    (net (code "57") (name "unconnected-(Q6-D-Pad4)") (class "Default")
      (node (ref "Q6") (pin "4") (pinfunction "D_4") (pintype "passive"))
    )
    (net (code "58") (name "unconnected-(U1-ALERT-Pad3)") (class "Default")
      (node (ref "U1") (pin "3") (pinfunction "ALERT_3") (pintype "bidirectional"))
    )
    (net (code "59") (name "unconnected-(X2-Pad4)") (class "Default")
      (node (ref "X2") (pin "4") (pinfunction "4_4") (pintype "passive"))
    )
  )
)
